# NeuWatch.net
KiCad netlist of a schematic drawn in EAGLE
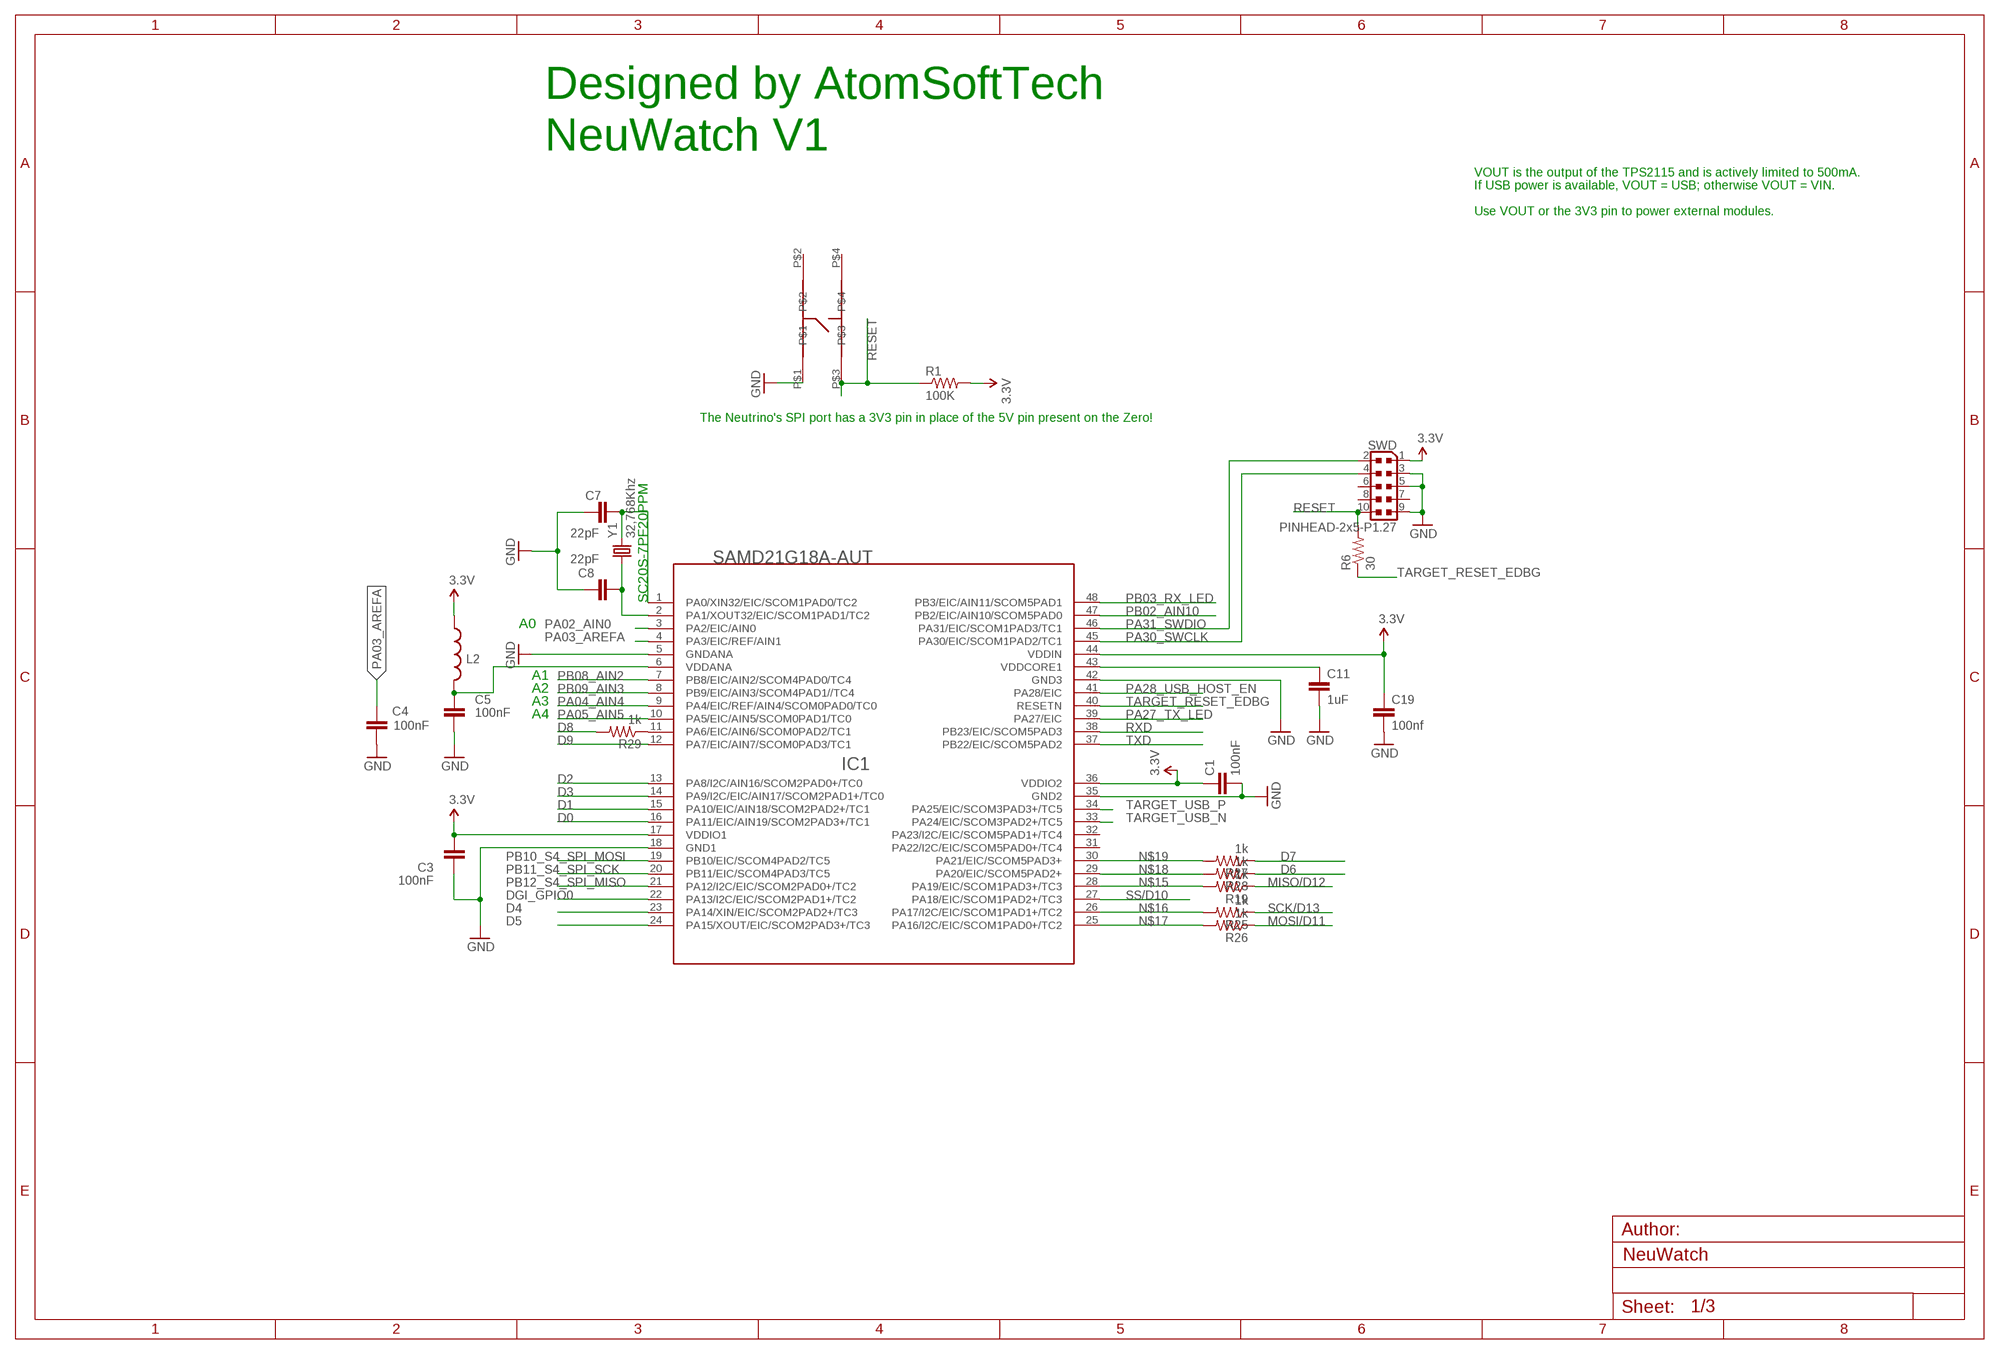
[diagram p0: schematic, sheet 1]
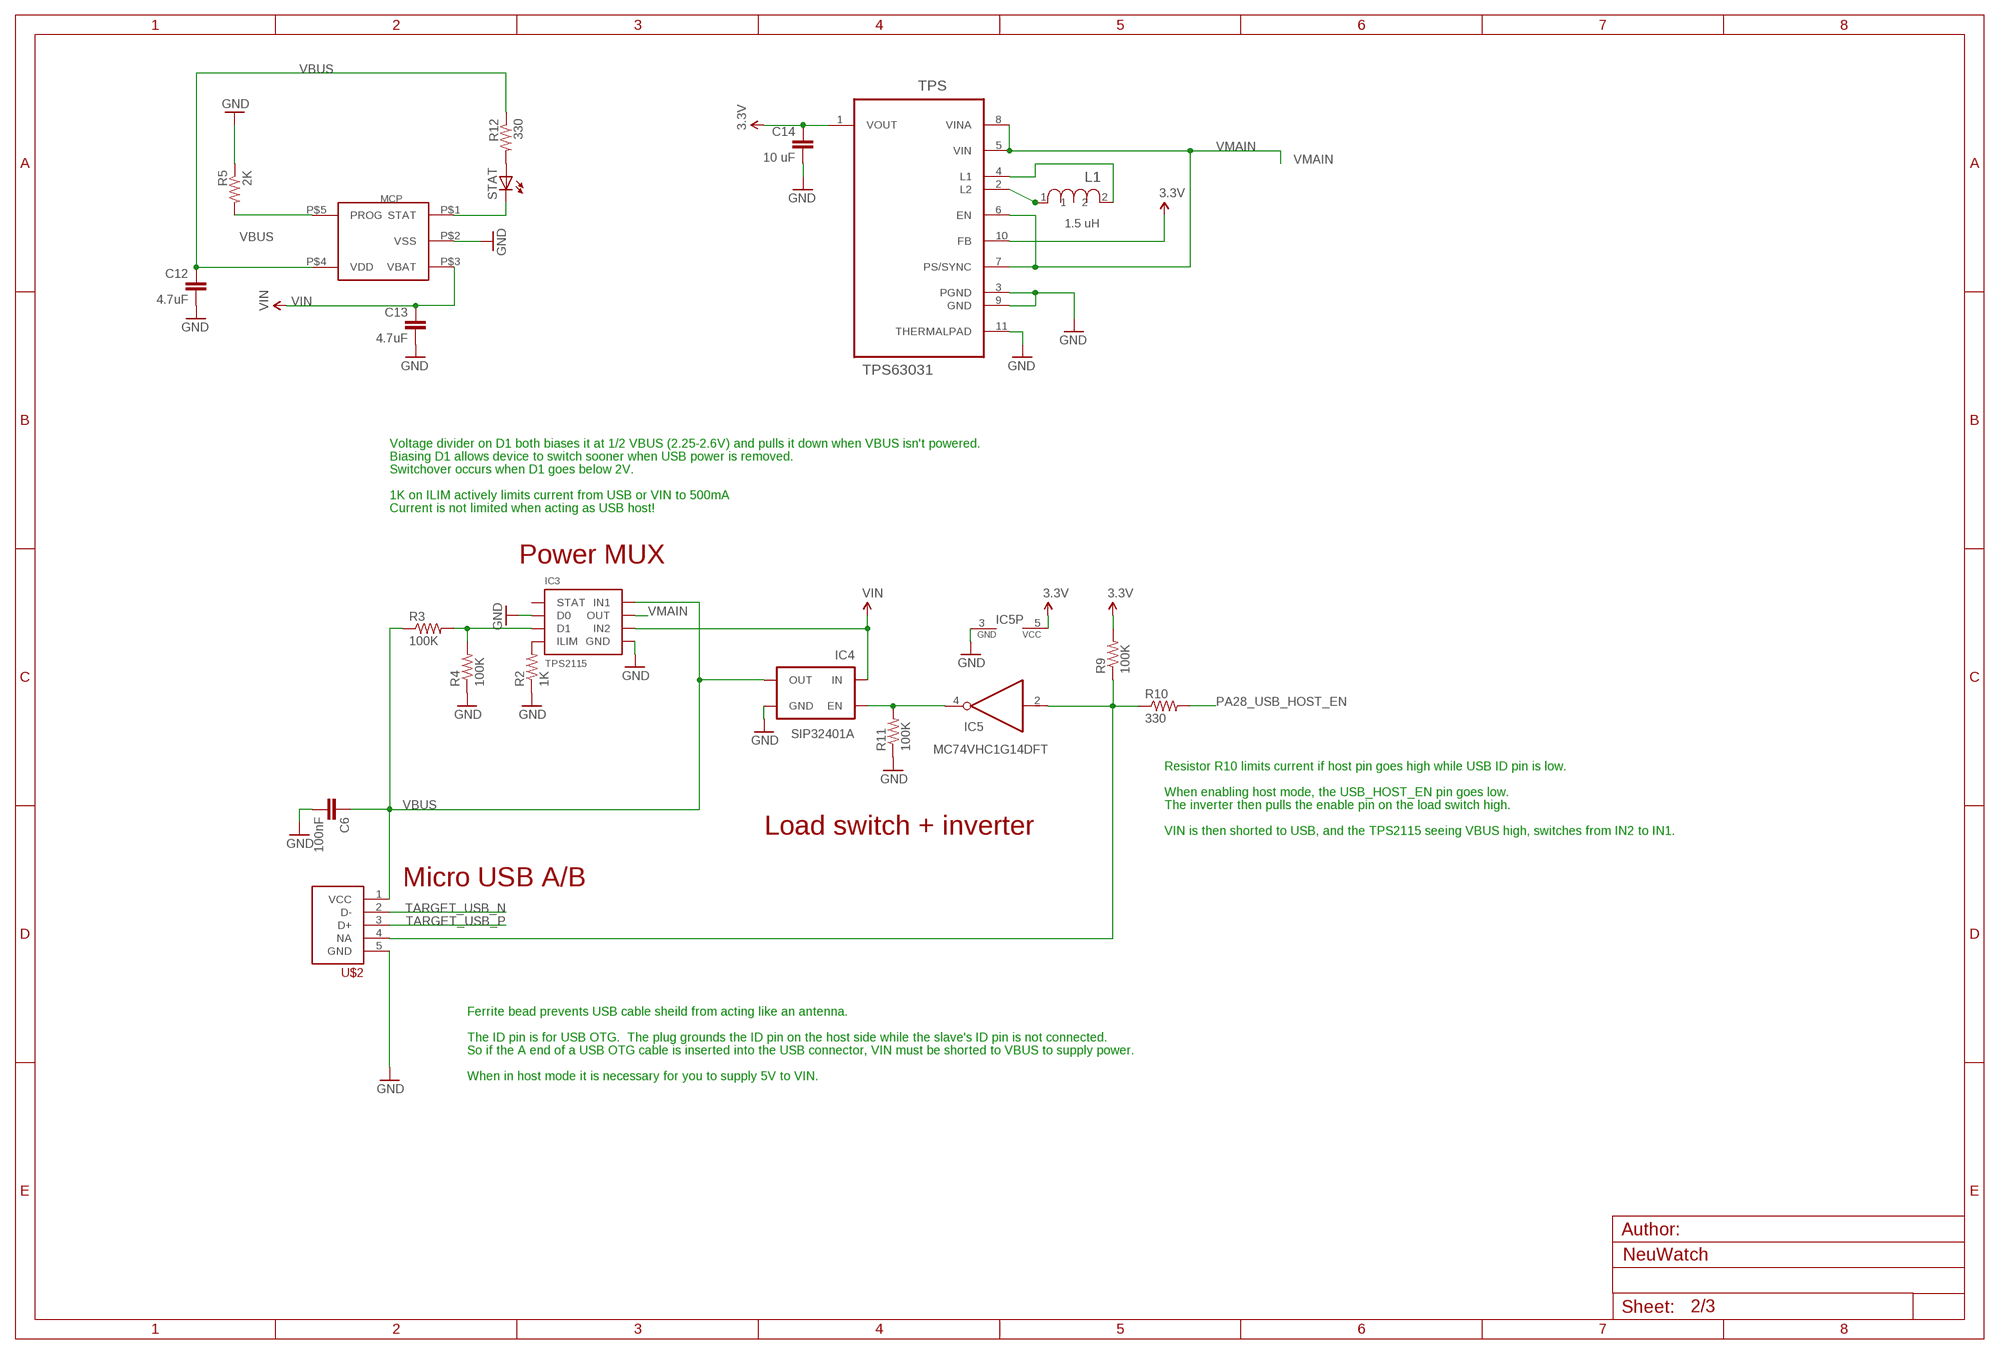
[diagram p1: schematic, sheet 2]
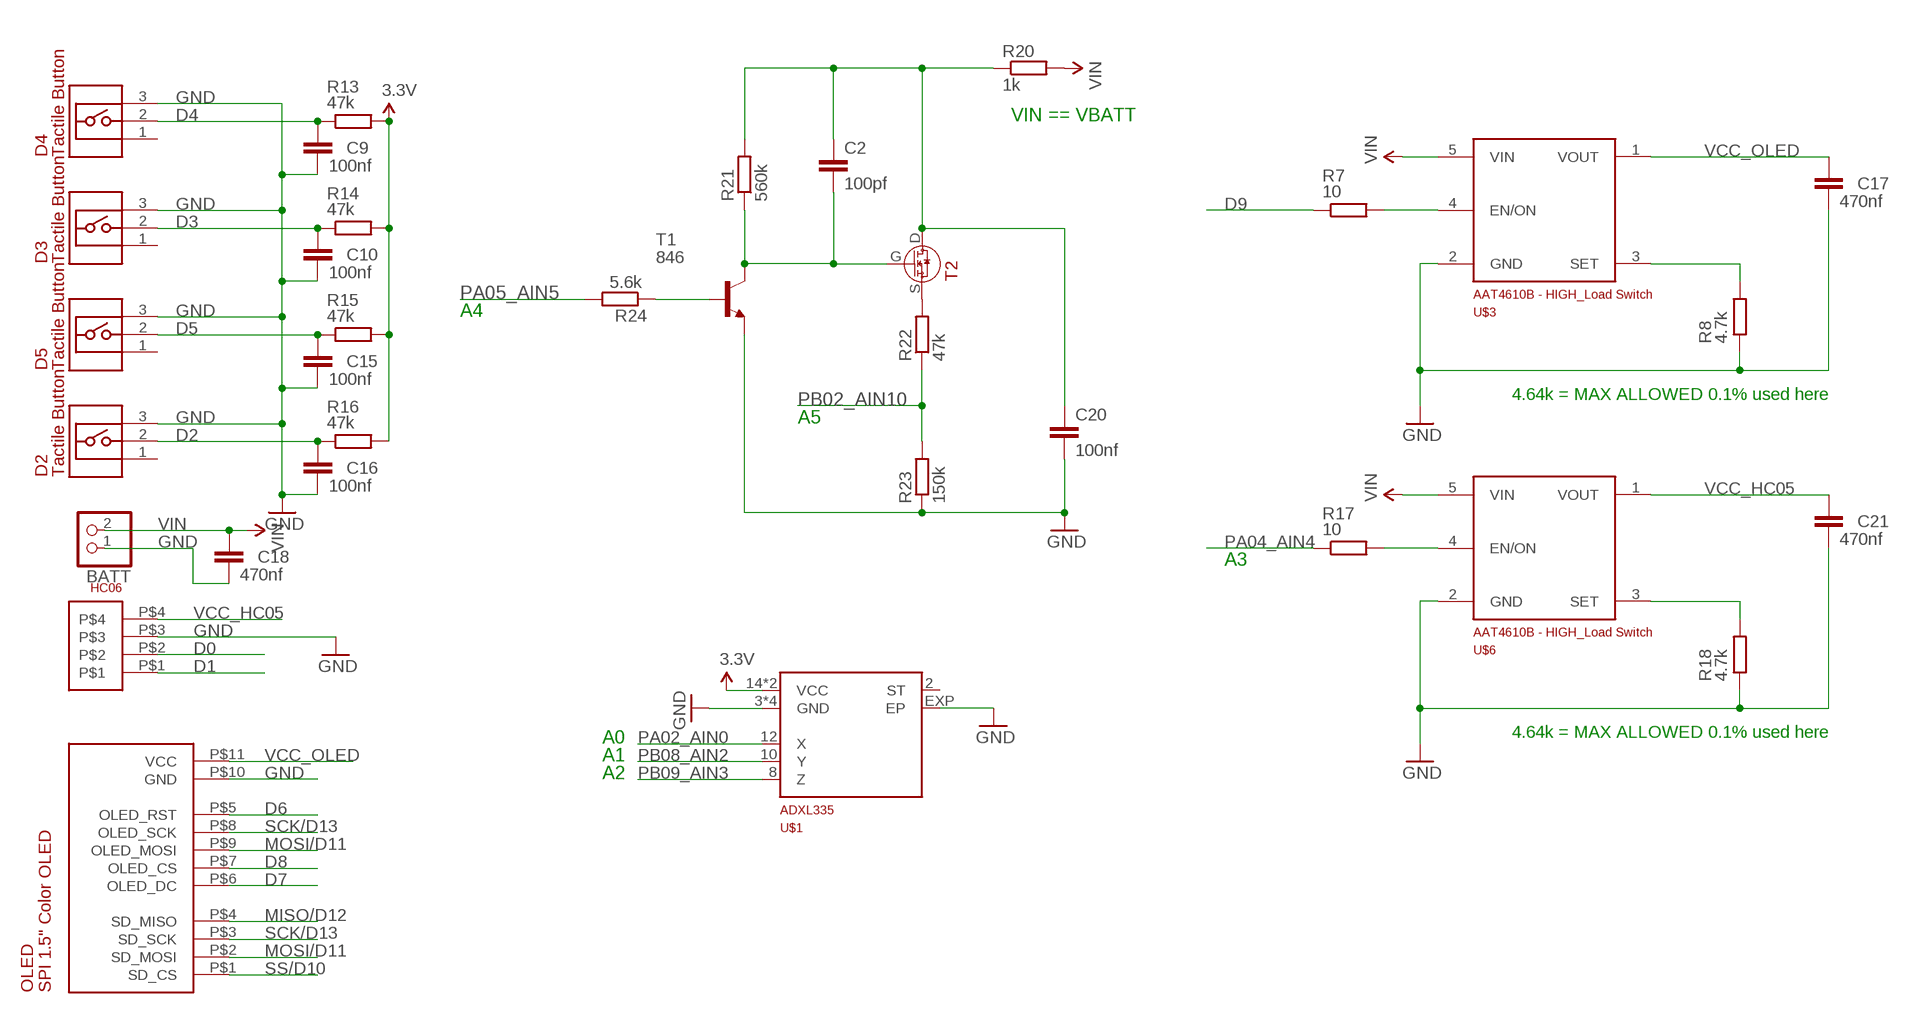
[diagram p2: schematic, sheet 3]

(export (version "E")
  (design (tool "Eeschema 10.0.6"))
  (components
    (comp (ref "C1")
      (value "100nF")
      (footprint "eagle-import:C0402")
      (libsource (lib "eagle-import") (part "CAPACITORC0402"))
    )
    (comp (ref "C3")
      (value "100nF")
      (footprint "eagle-import:C0402")
      (libsource (lib "eagle-import") (part "CAPACITORC0402"))
    )
    (comp (ref "C4")
      (value "100nF")
      (footprint "eagle-import:C0402")
      (libsource (lib "eagle-import") (part "CAPACITORC0402"))
    )
    (comp (ref "C5")
      (value "100nF")
      (footprint "eagle-import:C0402")
      (libsource (lib "eagle-import") (part "CAPACITORC0402"))
    )
    (comp (ref "C7")
      (value "22pF")
      (footprint "eagle-import:C0402")
      (libsource (lib "eagle-import") (part "CAPACITORC0402"))
    )
    (comp (ref "C8")
      (value "22pF")
      (footprint "eagle-import:C0402")
      (libsource (lib "eagle-import") (part "CAPACITORC0402"))
    )
    (comp (ref "C11")
      (value "1uF")
      (footprint "eagle-import:C0402")
      (libsource (lib "eagle-import") (part "CAPACITORC0402"))
    )
    (comp (ref "C19")
      (value "100nf")
      (footprint "eagle-import:C0402")
      (libsource (lib "eagle-import") (part "CAPACITORC0402"))
    )
    (comp (ref "IC1")
      (value "SAMD21G18A-AUT")
      (footprint "eagle-import:INTEGRATEDCIRCUITS_TQFP48-7X7")
      (libsource (lib "eagle-import") (part "INTEGRATEDCIRCUITS_1792_SAMD21G18A-AUT"))
    )
    (comp (ref "L2")
      (value "INDUCTOR0603-TDK")
      (footprint "eagle-import:0603-TDK")
      (libsource (lib "eagle-import") (part "INDUCTOR0603-TDK"))
    )
    (comp (ref "R1")
      (value "100K")
      (footprint "eagle-import:R0402")
      (libsource (lib "eagle-import") (part "R-US_R0402"))
    )
    (comp (ref "R6")
      (value "30")
      (footprint "eagle-import:R0402")
      (libsource (lib "eagle-import") (part "R-US_R0402"))
    )
    (comp (ref "R19")
      (value "1k")
      (footprint "eagle-import:R0402")
      (libsource (lib "eagle-import") (part "R-US_R0402"))
    )
    (comp (ref "R25")
      (value "1k")
      (footprint "eagle-import:R0402")
      (libsource (lib "eagle-import") (part "R-US_R0402"))
    )
    (comp (ref "R26")
      (value "1k")
      (footprint "eagle-import:R0402")
      (libsource (lib "eagle-import") (part "R-US_R0402"))
    )
    (comp (ref "R27")
      (value "1k")
      (footprint "eagle-import:R0402")
      (libsource (lib "eagle-import") (part "R-US_R0402"))
    )
    (comp (ref "R28")
      (value "1k")
      (footprint "eagle-import:R0402")
      (libsource (lib "eagle-import") (part "R-US_R0402"))
    )
    (comp (ref "R29")
      (value "1k")
      (footprint "eagle-import:R0402")
      (libsource (lib "eagle-import") (part "R-US_R0402"))
    )
    (comp (ref "RESET")
      (value "TACTILE_SWITCH")
      (footprint "eagle-import:PTS540")
      (libsource (lib "eagle-import") (part "TACTILE_SWITCH"))
    )
    (comp (ref "SWD")
      (value "PINHEAD-2x5-P1.27")
      (footprint "eagle-import:ARDUINO-NEUTRINO-082_CONNETTORI_PINHEAD-2X5-P127")
      (libsource (lib "eagle-import") (part "ARDUINO-NEUTRINO-082_CONNETTORI_0171_PH127-205DF055G00A"))
    )
    (comp (ref "Y1")
      (value "32,768Khz")
      (footprint "eagle-import:CRYSTAL-SMD-2.0X1.2")
      (libsource (lib "eagle-import") (part "CRYSTAL2012"))
    )
    (comp (ref "C6")
      (value "100nF")
      (footprint "eagle-import:C0402")
      (libsource (lib "eagle-import") (part "CAPACITORC0402"))
    )
    (comp (ref "C12")
      (value "4.7uF")
      (footprint "eagle-import:C0402")
      (libsource (lib "eagle-import") (part "CAPACITORC0402"))
    )
    (comp (ref "C13")
      (value "4.7uF")
      (footprint "eagle-import:C0402")
      (libsource (lib "eagle-import") (part "CAPACITORC0402"))
    )
    (comp (ref "C14")
      (value "10 uF")
      (footprint "eagle-import:C0402")
      (libsource (lib "eagle-import") (part "CAPACITORC0402"))
    )
    (comp (ref "IC3")
      (value "TPS2115")
      (footprint "eagle-import:8-VDFN")
      (libsource (lib "eagle-import") (part "TPS2115"))
    )
    (comp (ref "IC4")
      (value "SIP32401A")
      (footprint "eagle-import:TDFN4")
      (libsource (lib "eagle-import") (part "SIP32401A"))
    )
    (comp (ref "IC5")
      (value "MC74VHC1G14DFT")
      (footprint "eagle-import:SC70-5")
      (libsource (lib "eagle-import") (part "741G04DCKAHC"))
    )
    (comp (ref "L1")
      (value "1.5 uH")
      (footprint "eagle-import:INDC1610X12N")
      (fields (field (name "MPN") "PM0603-R12J-RC") (field (name "TOLERANCE") "±5 %"))
      (libsource (lib "eagle-import") (part "PM0603-R12J-RC"))
    )
    (comp (ref "MCP")
      (value "MCP73831")
      (footprint "eagle-import:5PIN_SOT23")
      (libsource (lib "eagle-import") (part "MCP73831"))
    )
    (comp (ref "R2")
      (value "1K")
      (footprint "eagle-import:R0402")
      (libsource (lib "eagle-import") (part "R-US_R0402"))
    )
    (comp (ref "R3")
      (value "100K")
      (footprint "eagle-import:R0402")
      (libsource (lib "eagle-import") (part "R-US_R0402"))
    )
    (comp (ref "R4")
      (value "100K")
      (footprint "eagle-import:R0402")
      (libsource (lib "eagle-import") (part "R-US_R0402"))
    )
    (comp (ref "R5")
      (value "2K")
      (footprint "eagle-import:R0402")
      (libsource (lib "eagle-import") (part "rcl_R-US_R0402"))
    )
    (comp (ref "R9")
      (value "100K")
      (footprint "eagle-import:R0402")
      (libsource (lib "eagle-import") (part "R-US_R0402"))
    )
    (comp (ref "R10")
      (value "330")
      (footprint "eagle-import:R0402")
      (libsource (lib "eagle-import") (part "R-US_R0402"))
    )
    (comp (ref "R11")
      (value "100K")
      (footprint "eagle-import:R0402")
      (libsource (lib "eagle-import") (part "R-US_R0402"))
    )
    (comp (ref "R12")
      (value "330")
      (footprint "eagle-import:R0402")
      (libsource (lib "eagle-import") (part "rcl_R-US_R0402"))
    )
    (comp (ref "STAT")
      (value "LEDSML0603")
      (footprint "eagle-import:SML0603")
      (libsource (lib "eagle-import") (part "LEDSML0603"))
    )
    (comp (ref "TPS")
      (value "TPS63031")
      (footprint "eagle-import:SON50P260X260X80-11N")
      (fields (field (name "MPN") "TPS63031"))
      (libsource (lib "eagle-import") (part "TPS63031"))
    )
    (comp (ref "U$2")
      (value "USB_GENERIC_CHEAT")
      (footprint "eagle-import:1LFS")
      (libsource (lib "eagle-import") (part "USB_GENERIC_CHEAT"))
    )
    (comp (ref "BATT")
      (value "PINHD-1X2")
      (footprint "eagle-import:1X02")
      (libsource (lib "eagle-import") (part "PINHD-1X2"))
    )
    (comp (ref "C2")
      (value "100pf")
      (footprint "eagle-import:C0402")
      (libsource (lib "eagle-import") (part "CAPACITORC0402"))
    )
    (comp (ref "C9")
      (value "100nf")
      (footprint "eagle-import:C0402")
      (libsource (lib "eagle-import") (part "CAPACITORC0402"))
    )
    (comp (ref "C10")
      (value "100nf")
      (footprint "eagle-import:C0402")
      (libsource (lib "eagle-import") (part "CAPACITORC0402"))
    )
    (comp (ref "C15")
      (value "100nf")
      (footprint "eagle-import:C0402")
      (libsource (lib "eagle-import") (part "CAPACITORC0402"))
    )
    (comp (ref "C16")
      (value "100nf")
      (footprint "eagle-import:C0402")
      (libsource (lib "eagle-import") (part "CAPACITORC0402"))
    )
    (comp (ref "C17")
      (value "470nf")
      (footprint "eagle-import:C0402")
      (libsource (lib "eagle-import") (part "CAPACITORC0402"))
    )
    (comp (ref "C18")
      (value "470nf")
      (footprint "eagle-import:C0402")
      (libsource (lib "eagle-import") (part "CAPACITORC0402"))
    )
    (comp (ref "C20")
      (value "100nf")
      (footprint "eagle-import:C0402")
      (libsource (lib "eagle-import") (part "CAPACITORC0402"))
    )
    (comp (ref "C21")
      (value "470nf")
      (footprint "eagle-import:C0402")
      (libsource (lib "eagle-import") (part "CAPACITORC0402"))
    )
    (comp (ref "D2")
      (value "BUTTON_P0")
      (footprint "eagle-import:P021301")
      (libsource (lib "eagle-import") (part "BUTTON_P0"))
    )
    (comp (ref "D3")
      (value "BUTTON_P0")
      (footprint "eagle-import:P021301")
      (libsource (lib "eagle-import") (part "BUTTON_P0"))
    )
    (comp (ref "D4")
      (value "BUTTON_P0")
      (footprint "eagle-import:P021301")
      (libsource (lib "eagle-import") (part "BUTTON_P0"))
    )
    (comp (ref "D5")
      (value "BUTTON_P0")
      (footprint "eagle-import:P021301")
      (libsource (lib "eagle-import") (part "BUTTON_P0"))
    )
    (comp (ref "HC06")
      (value "1X4")
      (footprint "eagle-import:1B4")
      (libsource (lib "eagle-import") (part "1X4"))
    )
    (comp (ref "OLED")
      (value "1.5-OLED")
      (footprint "eagle-import:1.5OLED")
      (libsource (lib "eagle-import") (part "1.5-OLED"))
    )
    (comp (ref "R7")
      (value "10")
      (footprint "eagle-import:R0402")
      (libsource (lib "eagle-import") (part "R-EU_R0402"))
    )
    (comp (ref "R8")
      (value "4.7k")
      (footprint "eagle-import:R0402")
      (libsource (lib "eagle-import") (part "R-EU_R0402"))
    )
    (comp (ref "R13")
      (value "47k")
      (footprint "eagle-import:R0402")
      (libsource (lib "eagle-import") (part "R-EU_R0402"))
    )
    (comp (ref "R14")
      (value "47k")
      (footprint "eagle-import:R0402")
      (libsource (lib "eagle-import") (part "R-EU_R0402"))
    )
    (comp (ref "R15")
      (value "47k")
      (footprint "eagle-import:R0402")
      (libsource (lib "eagle-import") (part "R-EU_R0402"))
    )
    (comp (ref "R16")
      (value "47k")
      (footprint "eagle-import:R0402")
      (libsource (lib "eagle-import") (part "R-EU_R0402"))
    )
    (comp (ref "R17")
      (value "10")
      (footprint "eagle-import:R0402")
      (libsource (lib "eagle-import") (part "R-EU_R0402"))
    )
    (comp (ref "R18")
      (value "4.7k")
      (footprint "eagle-import:R0402")
      (libsource (lib "eagle-import") (part "R-EU_R0402"))
    )
    (comp (ref "R20")
      (value "1k")
      (footprint "eagle-import:R0402")
      (libsource (lib "eagle-import") (part "R-EU_R0402"))
    )
    (comp (ref "R21")
      (value "560k")
      (footprint "eagle-import:R0402")
      (libsource (lib "eagle-import") (part "R-EU_R0402"))
    )
    (comp (ref "R22")
      (value "47k")
      (footprint "eagle-import:R0402")
      (libsource (lib "eagle-import") (part "R-EU_R0402"))
    )
    (comp (ref "R23")
      (value "150k")
      (footprint "eagle-import:R0402")
      (libsource (lib "eagle-import") (part "R-EU_R0402"))
    )
    (comp (ref "R24")
      (value "5.6k")
      (footprint "eagle-import:R0402")
      (libsource (lib "eagle-import") (part "R-EU_R0402"))
    )
    (comp (ref "T1")
      (value "846")
      (footprint "eagle-import:SOT23-BEC")
      (libsource (lib "eagle-import") (part "-NPN-SOT23-BECBC846BLT1"))
    )
    (comp (ref "T2")
      (value "2N7002")
      (footprint "eagle-import:MOSFET")
      (libsource (lib "eagle-import") (part "2N7002_ALT"))
    )
    (comp (ref "U$1")
      (value "ADXL335")
      (footprint "eagle-import:16LFCSP")
      (libsource (lib "eagle-import") (part "ADXL335"))
    )
    (comp (ref "U$3")
      (value "AAT4610B")
      (footprint "eagle-import:SOT23-5")
      (libsource (lib "eagle-import") (part "AAT4610B"))
    )
    (comp (ref "U$6")
      (value "AAT4610B")
      (footprint "eagle-import:SOT23-5")
      (libsource (lib "eagle-import") (part "AAT4610B"))
    )
  )
  (nets
    (net (code "1") (name "3.3V") (class "Default")
      (node (ref "C1") (pin "1") (pinfunction "1_1") (pintype "passive"))
      (node (ref "C14") (pin "1") (pinfunction "1_1") (pintype "passive"))
      (node (ref "C19") (pin "1") (pinfunction "1_1") (pintype "passive"))
      (node (ref "C3") (pin "2") (pinfunction "2_2") (pintype "passive"))
      (node (ref "IC1") (pin "17") (pinfunction "VDDIO1_17") (pintype "power_in"))
      (node (ref "IC1") (pin "36") (pinfunction "VDDIO2_36") (pintype "power_in"))
      (node (ref "IC1") (pin "44") (pinfunction "VDDIN_44") (pintype "power_in"))
      (node (ref "IC5") (pin "5") (pinfunction "VCC_5") (pintype "power_in"))
      (node (ref "L2") (pin "1") (pinfunction "1_1") (pintype "passive"))
      (node (ref "R1") (pin "2") (pinfunction "2_2") (pintype "passive"))
      (node (ref "R13") (pin "2") (pinfunction "2_2") (pintype "passive"))
      (node (ref "R14") (pin "2") (pinfunction "2_2") (pintype "passive"))
      (node (ref "R15") (pin "2") (pinfunction "2_2") (pintype "passive"))
      (node (ref "R16") (pin "2") (pinfunction "2_2") (pintype "passive"))
      (node (ref "R9") (pin "2") (pinfunction "2_2") (pintype "passive"))
      (node (ref "SWD") (pin "1") (pinfunction "1_1") (pintype "passive"))
      (node (ref "TPS") (pin "1") (pinfunction "VOUT_1") (pintype "output"))
      (node (ref "TPS") (pin "10") (pinfunction "FB_10") (pintype "input"))
      (node (ref "U$1") (pin "14") (pinfunction "VCC_14") (pintype "power_in"))
      (node (ref "U$1") (pin "15") (pinfunction "VCC_15") (pintype "power_in"))
    )
    (net (code "2") (name "D0") (class "Default")
      (node (ref "HC06") (pin "P$2") (pinfunction "P$2_P$2") (pintype "bidirectional"))
      (node (ref "IC1") (pin "16") (pinfunction "PA11/EIC/AIN19/SCOM2PAD3+/TC1_16") (pintype "bidirectional"))
    )
    (net (code "3") (name "D1") (class "Default")
      (node (ref "HC06") (pin "P$1") (pinfunction "P$1_P$1") (pintype "bidirectional"))
      (node (ref "IC1") (pin "15") (pinfunction "PA10/EIC/AIN18/SCOM2PAD2+/TC1_15") (pintype "bidirectional"))
    )
    (net (code "4") (name "D2") (class "Default")
      (node (ref "C16") (pin "1") (pinfunction "1_1") (pintype "passive"))
      (node (ref "D2") (pin "2") (pinfunction "2_2") (pintype "bidirectional"))
      (node (ref "IC1") (pin "13") (pinfunction "PA8/I2C/AIN16/SCOM2PAD0+/TC0_13") (pintype "bidirectional"))
      (node (ref "R16") (pin "1") (pinfunction "1_1") (pintype "passive"))
    )
    (net (code "5") (name "D3") (class "Default")
      (node (ref "C10") (pin "1") (pinfunction "1_1") (pintype "passive"))
      (node (ref "D3") (pin "2") (pinfunction "2_2") (pintype "bidirectional"))
      (node (ref "IC1") (pin "14") (pinfunction "PA9/I2C/EIC/AIN17/SCOM2PAD1+/TC0_14") (pintype "bidirectional"))
      (node (ref "R14") (pin "1") (pinfunction "1_1") (pintype "passive"))
    )
    (net (code "6") (name "D4") (class "Default")
      (node (ref "C9") (pin "1") (pinfunction "1_1") (pintype "passive"))
      (node (ref "D4") (pin "2") (pinfunction "2_2") (pintype "bidirectional"))
      (node (ref "IC1") (pin "23") (pinfunction "PA14/XIN/EIC/SCOM2PAD2+/TC3_23") (pintype "bidirectional"))
      (node (ref "R13") (pin "1") (pinfunction "1_1") (pintype "passive"))
    )
    (net (code "7") (name "D5") (class "Default")
      (node (ref "C15") (pin "1") (pinfunction "1_1") (pintype "passive"))
      (node (ref "D5") (pin "2") (pinfunction "2_2") (pintype "bidirectional"))
      (node (ref "IC1") (pin "24") (pinfunction "PA15/XOUT/EIC/SCOM2PAD3+/TC3_24") (pintype "bidirectional"))
      (node (ref "R15") (pin "1") (pinfunction "1_1") (pintype "passive"))
    )
    (net (code "8") (name "D6") (class "Default")
      (node (ref "OLED") (pin "P$5") (pinfunction "OLED_RST_P$5") (pintype "bidirectional"))
      (node (ref "R28") (pin "1") (pinfunction "1_1") (pintype "passive"))
    )
    (net (code "9") (name "D7") (class "Default")
      (node (ref "OLED") (pin "P$6") (pinfunction "OLED_DC_P$6") (pintype "bidirectional"))
      (node (ref "R27") (pin "1") (pinfunction "1_1") (pintype "passive"))
    )
    (net (code "10") (name "D8") (class "Default")
      (node (ref "OLED") (pin "P$7") (pinfunction "OLED_CS_P$7") (pintype "bidirectional"))
      (node (ref "R29") (pin "2") (pinfunction "2_2") (pintype "passive"))
    )
    (net (code "11") (name "D9") (class "Default")
      (node (ref "IC1") (pin "12") (pinfunction "PA7/EIC/AIN7/SCOM0PAD3/TC1_12") (pintype "bidirectional"))
      (node (ref "R7") (pin "1") (pinfunction "1_1") (pintype "passive"))
    )
    (net (code "12") (name "DGI_GPIO0") (class "Default")
      (node (ref "IC1") (pin "22") (pinfunction "PA13/I2C/EIC/SCOM2PAD1+/TC2_22") (pintype "bidirectional"))
    )
    (net (code "13") (name "GND") (class "Default")
      (node (ref "BATT") (pin "1") (pinfunction "1_1") (pintype "passive"))
      (node (ref "C1") (pin "2") (pinfunction "2_2") (pintype "passive"))
      (node (ref "C10") (pin "2") (pinfunction "2_2") (pintype "passive"))
      (node (ref "C11") (pin "2") (pinfunction "2_2") (pintype "passive"))
      (node (ref "C12") (pin "2") (pinfunction "2_2") (pintype "passive"))
      (node (ref "C13") (pin "2") (pinfunction "2_2") (pintype "passive"))
      (node (ref "C14") (pin "2") (pinfunction "2_2") (pintype "passive"))
      (node (ref "C15") (pin "2") (pinfunction "2_2") (pintype "passive"))
      (node (ref "C16") (pin "2") (pinfunction "2_2") (pintype "passive"))
      (node (ref "C17") (pin "2") (pinfunction "2_2") (pintype "passive"))
      (node (ref "C18") (pin "2") (pinfunction "2_2") (pintype "passive"))
      (node (ref "C19") (pin "2") (pinfunction "2_2") (pintype "passive"))
      (node (ref "C20") (pin "2") (pinfunction "2_2") (pintype "passive"))
      (node (ref "C21") (pin "2") (pinfunction "2_2") (pintype "passive"))
      (node (ref "C3") (pin "1") (pinfunction "1_1") (pintype "passive"))
      (node (ref "C4") (pin "2") (pinfunction "2_2") (pintype "passive"))
      (node (ref "C5") (pin "2") (pinfunction "2_2") (pintype "passive"))
      (node (ref "C6") (pin "2") (pinfunction "2_2") (pintype "passive"))
      (node (ref "C7") (pin "1") (pinfunction "1_1") (pintype "passive"))
      (node (ref "C8") (pin "1") (pinfunction "1_1") (pintype "passive"))
      (node (ref "C9") (pin "2") (pinfunction "2_2") (pintype "passive"))
      (node (ref "D2") (pin "3") (pinfunction "3_3") (pintype "bidirectional"))
      (node (ref "D3") (pin "3") (pinfunction "3_3") (pintype "bidirectional"))
      (node (ref "D4") (pin "3") (pinfunction "3_3") (pintype "bidirectional"))
      (node (ref "D5") (pin "3") (pinfunction "3_3") (pintype "bidirectional"))
      (node (ref "HC06") (pin "P$3") (pinfunction "P$3_P$3") (pintype "bidirectional"))
      (node (ref "IC1") (pin "18") (pinfunction "GND1_18") (pintype "power_in"))
      (node (ref "IC1") (pin "35") (pinfunction "GND2_35") (pintype "power_in"))
      (node (ref "IC1") (pin "42") (pinfunction "GND3_42") (pintype "power_in"))
      (node (ref "IC1") (pin "5") (pinfunction "GNDANA_5") (pintype "power_in"))
      (node (ref "IC3") (pin "2") (pinfunction "D0_2") (pintype "bidirectional"))
      (node (ref "IC3") (pin "5") (pinfunction "GND_5") (pintype "bidirectional"))
      (node (ref "IC3") (pin "P0") (pinfunction "GND_P0") (pintype "bidirectional"))
      (node (ref "IC3") (pin "V0") (pinfunction "GND_V0") (pintype "bidirectional"))
      (node (ref "IC3") (pin "V1") (pinfunction "GND_V1") (pintype "bidirectional"))
      (node (ref "IC3") (pin "V2") (pinfunction "GND_V2") (pintype "bidirectional"))
      (node (ref "IC3") (pin "V3") (pinfunction "GND_V3") (pintype "bidirectional"))
      (node (ref "IC3") (pin "V4") (pinfunction "GND_V4") (pintype "bidirectional"))
      (node (ref "IC4") (pin "0") (pinfunction "GND_0") (pintype "power_in"))
      (node (ref "IC4") (pin "2") (pinfunction "GND_2") (pintype "power_in"))
      (node (ref "IC5") (pin "3") (pinfunction "GND_3") (pintype "power_in"))
      (node (ref "MCP") (pin "P$2") (pinfunction "VSS_P$2") (pintype "bidirectional"))
      (node (ref "OLED") (pin "P$10") (pinfunction "GND_P$10") (pintype "bidirectional"))
      (node (ref "R11") (pin "1") (pinfunction "1_1") (pintype "passive"))
      (node (ref "R18") (pin "1") (pinfunction "1_1") (pintype "passive"))
      (node (ref "R2") (pin "1") (pinfunction "1_1") (pintype "passive"))
      (node (ref "R23") (pin "1") (pinfunction "1_1") (pintype "passive"))
      (node (ref "R4") (pin "1") (pinfunction "1_1") (pintype "passive"))
      (node (ref "R5") (pin "1") (pinfunction "1_1") (pintype "passive"))
      (node (ref "R8") (pin "1") (pinfunction "1_1") (pintype "passive"))
      (node (ref "RESET") (pin "P$1") (pinfunction "P$1_P$1") (pintype "bidirectional"))
      (node (ref "SWD") (pin "3") (pinfunction "3_3") (pintype "passive"))
      (node (ref "SWD") (pin "5") (pinfunction "5_5") (pintype "passive"))
      (node (ref "SWD") (pin "9") (pinfunction "9_9") (pintype "passive"))
      (node (ref "T1") (pin "E") (pinfunction "E_E") (pintype "passive"))
      (node (ref "TPS") (pin "11") (pinfunction "THERMALPAD_11") (pintype "passive"))
      (node (ref "TPS") (pin "3") (pinfunction "PGND_3") (pintype "passive"))
      (node (ref "TPS") (pin "9") (pinfunction "GND_9") (pintype "passive"))
      (node (ref "U$1") (pin "3") (pinfunction "GND_3") (pintype "power_in"))
      (node (ref "U$1") (pin "5") (pinfunction "GND_5") (pintype "power_in"))
      (node (ref "U$1") (pin "6") (pinfunction "GND_6") (pintype "power_in"))
      (node (ref "U$1") (pin "7") (pinfunction "GND_7") (pintype "power_in"))
      (node (ref "U$1") (pin "EXP") (pinfunction "EP_EXP") (pintype "power_in"))
      (node (ref "U$2") (pin "5") (pinfunction "GND_5") (pintype "bidirectional"))
      (node (ref "U$3") (pin "2") (pinfunction "GND_2") (pintype "bidirectional"))
      (node (ref "U$6") (pin "2") (pinfunction "GND_2") (pintype "bidirectional"))
    )
    (net (code "14") (name "MISO{slash}D12") (class "Default")
      (node (ref "OLED") (pin "P$4") (pinfunction "SD_MISO_P$4") (pintype "bidirectional"))
      (node (ref "R19") (pin "1") (pinfunction "1_1") (pintype "passive"))
    )
    (net (code "15") (name "MOSI{slash}D11") (class "Default")
      (node (ref "OLED") (pin "P$2") (pinfunction "SD_MOSI_P$2") (pintype "bidirectional"))
      (node (ref "OLED") (pin "P$9") (pinfunction "OLED_MOSI_P$9") (pintype "bidirectional"))
      (node (ref "R26") (pin "1") (pinfunction "1_1") (pintype "passive"))
    )
    (net (code "16") (name "N$15") (class "Default")
      (node (ref "IC1") (pin "28") (pinfunction "PA19/EIC/SCOM1PAD3+/TC3_28") (pintype "bidirectional"))
      (node (ref "R19") (pin "2") (pinfunction "2_2") (pintype "passive"))
    )
    (net (code "17") (name "N$16") (class "Default")
      (node (ref "IC1") (pin "26") (pinfunction "PA17/I2C/EIC/SCOM1PAD1+/TC2_26") (pintype "bidirectional"))
      (node (ref "R25") (pin "2") (pinfunction "2_2") (pintype "passive"))
    )
    (net (code "18") (name "N$17") (class "Default")
      (node (ref "IC1") (pin "25") (pinfunction "PA16/I2C/EIC/SCOM1PAD0+/TC2_25") (pintype "bidirectional"))
      (node (ref "R26") (pin "2") (pinfunction "2_2") (pintype "passive"))
    )
    (net (code "19") (name "N$18") (class "Default")
      (node (ref "IC1") (pin "29") (pinfunction "PA20/EIC/SCOM5PAD2+_29") (pintype "bidirectional"))
      (node (ref "R28") (pin "2") (pinfunction "2_2") (pintype "passive"))
    )
    (net (code "20") (name "N$19") (class "Default")
      (node (ref "IC1") (pin "30") (pinfunction "PA21/EIC/SCOM5PAD3+_30") (pintype "bidirectional"))
      (node (ref "R27") (pin "2") (pinfunction "2_2") (pintype "passive"))
    )
    (net (code "21") (name "Net-(C2-Pad1)") (class "Default")
      (node (ref "C2") (pin "1") (pinfunction "1_1") (pintype "passive"))
      (node (ref "C20") (pin "1") (pinfunction "1_1") (pintype "passive"))
      (node (ref "R20") (pin "1") (pinfunction "1_1") (pintype "passive"))
      (node (ref "R21") (pin "2") (pinfunction "2_2") (pintype "passive"))
      (node (ref "T2") (pin "D") (pinfunction "D_D") (pintype "bidirectional"))
    )
    (net (code "22") (name "Net-(C2-Pad2)") (class "Default")
      (node (ref "C2") (pin "2") (pinfunction "2_2") (pintype "passive"))
      (node (ref "R21") (pin "1") (pinfunction "1_1") (pintype "passive"))
      (node (ref "T1") (pin "C") (pinfunction "C_C") (pintype "passive"))
      (node (ref "T2") (pin "G") (pinfunction "G_G") (pintype "bidirectional"))
    )
    (net (code "23") (name "Net-(IC1-PA0{slash}XIN32{slash}EIC{slash}SCOM1PAD0{slash}TC2)") (class "Default")
      (node (ref "C7") (pin "2") (pinfunction "2_2") (pintype "passive"))
      (node (ref "IC1") (pin "1") (pinfunction "PA0/XIN32/EIC/SCOM1PAD0/TC2_1") (pintype "bidirectional"))
      (node (ref "Y1") (pin "2") (pinfunction "2_2") (pintype "passive"))
    )
    (net (code "24") (name "Net-(IC1-PA1{slash}XOUT32{slash}EIC{slash}SCOM1PAD1{slash}TC2)") (class "Default")
      (node (ref "C8") (pin "2") (pinfunction "2_2") (pintype "passive"))
      (node (ref "IC1") (pin "2") (pinfunction "PA1/XOUT32/EIC/SCOM1PAD1/TC2_2") (pintype "bidirectional"))
      (node (ref "Y1") (pin "1") (pinfunction "1_1") (pintype "passive"))
    )
    (net (code "25") (name "Net-(IC1-PA6{slash}EIC{slash}AIN6{slash}SCOM0PAD2{slash}TC1)") (class "Default")
      (node (ref "IC1") (pin "11") (pinfunction "PA6/EIC/AIN6/SCOM0PAD2/TC1_11") (pintype "bidirectional"))
      (node (ref "R29") (pin "1") (pinfunction "1_1") (pintype "passive"))
    )
    (net (code "26") (name "Net-(IC1-VDDANA)") (class "Default")
      (node (ref "C5") (pin "1") (pinfunction "1_1") (pintype "passive"))
      (node (ref "IC1") (pin "6") (pinfunction "VDDANA_6") (pintype "power_in"))
      (node (ref "L2") (pin "2") (pinfunction "2_2") (pintype "passive"))
    )
    (net (code "27") (name "Net-(IC1-VDDCORE1)") (class "Default")
      (node (ref "C11") (pin "1") (pinfunction "1_1") (pintype "passive"))
      (node (ref "IC1") (pin "43") (pinfunction "VDDCORE1_43") (pintype "input"))
    )
    (net (code "28") (name "Net-(IC3-D1)") (class "Default")
      (node (ref "IC3") (pin "3") (pinfunction "D1_3") (pintype "bidirectional"))
      (node (ref "R3") (pin "2") (pinfunction "2_2") (pintype "passive"))
      (node (ref "R4") (pin "2") (pinfunction "2_2") (pintype "passive"))
    )
    (net (code "29") (name "Net-(IC3-ILIM)") (class "Default")
      (node (ref "IC3") (pin "4") (pinfunction "ILIM_4") (pintype "bidirectional"))
      (node (ref "R2") (pin "2") (pinfunction "2_2") (pintype "passive"))
    )
    (net (code "30") (name "Net-(IC4-EN)") (class "Default")
      (node (ref "IC4") (pin "4") (pinfunction "EN_4") (pintype "input"))
      (node (ref "IC5") (pin "4") (pinfunction "O_4") (pintype "output"))
      (node (ref "R11") (pin "2") (pinfunction "2_2") (pintype "passive"))
    )
    (net (code "31") (name "Net-(IC5A-I)") (class "Default")
      (node (ref "IC5") (pin "2") (pinfunction "I_2") (pintype "input"))
      (node (ref "R10") (pin "1") (pinfunction "1_1") (pintype "passive"))
      (node (ref "R9") (pin "1") (pinfunction "1_1") (pintype "passive"))
      (node (ref "U$2") (pin "4") (pinfunction "NA_4") (pintype "bidirectional"))
    )
    (net (code "32") (name "Net-(MCP-PROG)") (class "Default")
      (node (ref "MCP") (pin "P$5") (pinfunction "PROG_P$5") (pintype "bidirectional"))
      (node (ref "R5") (pin "2") (pinfunction "2_2") (pintype "passive"))
    )
    (net (code "33") (name "Net-(MCP-STAT)") (class "Default")
      (node (ref "MCP") (pin "P$1") (pinfunction "STAT_P$1") (pintype "bidirectional"))
      (node (ref "STAT") (pin "C") (pinfunction "C_C") (pintype "passive"))
    )
    (net (code "34") (name "Net-(R12-Pad2)") (class "Default")
      (node (ref "R12") (pin "2") (pinfunction "2_2") (pintype "passive"))
      (node (ref "STAT") (pin "A") (pinfunction "A_A") (pintype "passive"))
    )
    (net (code "35") (name "Net-(R22-Pad2)") (class "Default")
      (node (ref "R22") (pin "2") (pinfunction "2_2") (pintype "passive"))
      (node (ref "T2") (pin "S") (pinfunction "S_S") (pintype "bidirectional"))
    )
    (net (code "36") (name "Net-(R24-Pad1)") (class "Default")
      (node (ref "R24") (pin "1") (pinfunction "1_1") (pintype "passive"))
      (node (ref "T1") (pin "B") (pinfunction "B_B") (pintype "passive"))
    )
    (net (code "37") (name "Net-(TPS-L1)") (class "Default")
      (node (ref "L1") (pin "2") (pinfunction "2_2") (pintype "passive"))
      (node (ref "TPS") (pin "4") (pinfunction "L1_4") (pintype "input"))
    )
    (net (code "38") (name "Net-(TPS-L2)") (class "Default")
      (node (ref "L1") (pin "1") (pinfunction "1_1") (pintype "passive"))
      (node (ref "TPS") (pin "2") (pinfunction "L2_2") (pintype "input"))
    )
    (net (code "39") (name "Net-(U$3-EN{slash}ON)") (class "Default")
      (node (ref "R7") (pin "2") (pinfunction "2_2") (pintype "passive"))
      (node (ref "U$3") (pin "4") (pinfunction "EN/ON_4") (pintype "bidirectional"))
    )
    (net (code "40") (name "Net-(U$3-SET)") (class "Default")
      (node (ref "R8") (pin "2") (pinfunction "2_2") (pintype "passive"))
      (node (ref "U$3") (pin "3") (pinfunction "SET_3") (pintype "bidirectional"))
    )
    (net (code "41") (name "Net-(U$6-EN{slash}ON)") (class "Default")
      (node (ref "R17") (pin "2") (pinfunction "2_2") (pintype "passive"))
      (node (ref "U$6") (pin "4") (pinfunction "EN/ON_4") (pintype "bidirectional"))
    )
    (net (code "42") (name "Net-(U$6-SET)") (class "Default")
      (node (ref "R18") (pin "2") (pinfunction "2_2") (pintype "passive"))
      (node (ref "U$6") (pin "3") (pinfunction "SET_3") (pintype "bidirectional"))
    )
    (net (code "43") (name "PA02_AIN0") (class "Default")
      (node (ref "IC1") (pin "3") (pinfunction "PA2/EIC/AIN0_3") (pintype "bidirectional"))
      (node (ref "U$1") (pin "12") (pinfunction "X_12") (pintype "power_in"))
    )
    (net (code "44") (name "PA03_AREFA") (class "Default")
      (node (ref "C4") (pin "1") (pinfunction "1_1") (pintype "passive"))
      (node (ref "IC1") (pin "4") (pinfunction "PA3/EIC/REF/AIN1_4") (pintype "bidirectional"))
    )
    (net (code "45") (name "PA04_AIN4") (class "Default")
      (node (ref "IC1") (pin "9") (pinfunction "PA4/EIC/REF/AIN4/SCOM0PAD0/TC0_9") (pintype "bidirectional"))
      (node (ref "R17") (pin "1") (pinfunction "1_1") (pintype "passive"))
    )
    (net (code "46") (name "PA05_AIN5") (class "Default")
      (node (ref "IC1") (pin "10") (pinfunction "PA5/EIC/AIN5/SCOM0PAD1/TC0_10") (pintype "bidirectional"))
      (node (ref "R24") (pin "2") (pinfunction "2_2") (pintype "passive"))
    )
    (net (code "47") (name "PA27_TX_LED") (class "Default")
      (node (ref "IC1") (pin "39") (pinfunction "PA27/EIC_39") (pintype "bidirectional"))
    )
    (net (code "48") (name "PA28_USB_HOST_EN") (class "Default")
      (node (ref "IC1") (pin "41") (pinfunction "PA28/EIC_41") (pintype "bidirectional"))
      (node (ref "R10") (pin "2") (pinfunction "2_2") (pintype "passive"))
    )
    (net (code "49") (name "PA30_SWCLK") (class "Default")
      (node (ref "IC1") (pin "45") (pinfunction "PA30/EIC/SCOM1PAD2/TC1_45") (pintype "bidirectional"))
      (node (ref "SWD") (pin "4") (pinfunction "4_4") (pintype "passive"))
    )
    (net (code "50") (name "PA31_SWDIO") (class "Default")
      (node (ref "IC1") (pin "46") (pinfunction "PA31/EIC/SCOM1PAD3/TC1_46") (pintype "bidirectional"))
      (node (ref "SWD") (pin "2") (pinfunction "2_2") (pintype "passive"))
    )
    (net (code "51") (name "PB02_AIN10") (class "Default")
      (node (ref "IC1") (pin "47") (pinfunction "PB2/EIC/AIN10/SCOM5PAD0_47") (pintype "bidirectional"))
      (node (ref "R22") (pin "1") (pinfunction "1_1") (pintype "passive"))
      (node (ref "R23") (pin "2") (pinfunction "2_2") (pintype "passive"))
    )
    (net (code "52") (name "PB03_RX_LED") (class "Default")
      (node (ref "IC1") (pin "48") (pinfunction "PB3/EIC/AIN11/SCOM5PAD1_48") (pintype "bidirectional"))
    )
    (net (code "53") (name "PB08_AIN2") (class "Default")
      (node (ref "IC1") (pin "7") (pinfunction "PB8/EIC/AIN2/SCOM4PAD0/TC4_7") (pintype "bidirectional"))
      (node (ref "U$1") (pin "10") (pinfunction "Y_10") (pintype "power_in"))
    )
    (net (code "54") (name "PB09_AIN3") (class "Default")
      (node (ref "IC1") (pin "8") (pinfunction "PB9/EIC/AIN3/SCOM4PAD1//TC4_8") (pintype "bidirectional"))
      (node (ref "U$1") (pin "8") (pinfunction "Z_8") (pintype "power_in"))
    )
    (net (code "55") (name "PB10_S4_SPI_MOSI") (class "Default")
      (node (ref "IC1") (pin "19") (pinfunction "PB10/EIC/SCOM4PAD2/TC5_19") (pintype "bidirectional"))
    )
    (net (code "56") (name "PB11_S4_SPI_SCK") (class "Default")
      (node (ref "IC1") (pin "20") (pinfunction "PB11/EIC/SCOM4PAD3/TC5_20") (pintype "bidirectional"))
    )
    (net (code "57") (name "PB12_S4_SPI_MISO") (class "Default")
      (node (ref "IC1") (pin "21") (pinfunction "PA12/I2C/EIC/SCOM2PAD0+/TC2_21") (pintype "bidirectional"))
    )
    (net (code "58") (name "RESET") (class "Default")
      (node (ref "R1") (pin "1") (pinfunction "1_1") (pintype "passive"))
      (node (ref "R6") (pin "2") (pinfunction "2_2") (pintype "passive"))
      (node (ref "RESET") (pin "P$3") (pinfunction "P$3_P$3") (pintype "bidirectional"))
      (node (ref "SWD") (pin "10") (pinfunction "10_10") (pintype "passive"))
    )
    (net (code "59") (name "RXD") (class "Default")
      (node (ref "IC1") (pin "38") (pinfunction "PB23/EIC/SCOM5PAD3_38") (pintype "bidirectional"))
    )
    (net (code "60") (name "SCK{slash}D13") (class "Default")
      (node (ref "OLED") (pin "P$3") (pinfunction "SD_SCK_P$3") (pintype "bidirectional"))
      (node (ref "OLED") (pin "P$8") (pinfunction "OLED_SCK_P$8") (pintype "bidirectional"))
      (node (ref "R25") (pin "1") (pinfunction "1_1") (pintype "passive"))
    )
    (net (code "61") (name "SS{slash}D10") (class "Default")
      (node (ref "IC1") (pin "27") (pinfunction "PA18/EIC/SCOM1PAD2+/TC3_27") (pintype "bidirectional"))
      (node (ref "OLED") (pin "P$1") (pinfunction "SD_CS_P$1") (pintype "bidirectional"))
    )
    (net (code "62") (name "ST") (class "Default")
      (node (ref "U$1") (pin "2") (pinfunction "ST_2") (pintype "power_in"))
    )
    (net (code "63") (name "TARGET_RESET_EDBG") (class "Default")
      (node (ref "IC1") (pin "40") (pinfunction "RESETN_40") (pintype "bidirectional"))
      (node (ref "R6") (pin "1") (pinfunction "1_1") (pintype "passive"))
    )
    (net (code "64") (name "TARGET_USB_N") (class "Default")
      (node (ref "IC1") (pin "33") (pinfunction "PA24/EIC/SCOM3PAD2+/TC5_33") (pintype "bidirectional"))
      (node (ref "U$2") (pin "2") (pinfunction "D-_2") (pintype "bidirectional"))
    )
    (net (code "65") (name "TARGET_USB_P") (class "Default")
      (node (ref "IC1") (pin "34") (pinfunction "PA25/EIC/SCOM3PAD3+/TC5_34") (pintype "bidirectional"))
      (node (ref "U$2") (pin "3") (pinfunction "D+_3") (pintype "bidirectional"))
    )
    (net (code "66") (name "TXD") (class "Default")
      (node (ref "IC1") (pin "37") (pinfunction "PB22/EIC/SCOM5PAD2_37") (pintype "bidirectional"))
    )
    (net (code "67") (name "VBUS") (class "Default")
      (node (ref "C12") (pin "1") (pinfunction "1_1") (pintype "passive"))
      (node (ref "C6") (pin "1") (pinfunction "1_1") (pintype "passive"))
      (node (ref "IC3") (pin "8") (pinfunction "IN1_8") (pintype "bidirectional"))
      (node (ref "IC4") (pin "1") (pinfunction "OUT_1") (pintype "power_in"))
      (node (ref "MCP") (pin "P$4") (pinfunction "VDD_P$4") (pintype "bidirectional"))
      (node (ref "R12") (pin "1") (pinfunction "1_1") (pintype "passive"))
      (node (ref "R3") (pin "1") (pinfunction "1_1") (pintype "passive"))
      (node (ref "U$2") (pin "1") (pinfunction "VCC_1") (pintype "bidirectional"))
    )
    (net (code "68") (name "VCC_HC05") (class "Default")
      (node (ref "C21") (pin "1") (pinfunction "1_1") (pintype "passive"))
      (node (ref "HC06") (pin "P$4") (pinfunction "P$4_P$4") (pintype "bidirectional"))
      (node (ref "U$6") (pin "1") (pinfunction "VOUT_1") (pintype "bidirectional"))
    )
    (net (code "69") (name "VCC_OLED") (class "Default")
      (node (ref "C17") (pin "1") (pinfunction "1_1") (pintype "passive"))
      (node (ref "OLED") (pin "P$11") (pinfunction "VCC_P$11") (pintype "bidirectional"))
      (node (ref "U$3") (pin "1") (pinfunction "VOUT_1") (pintype "bidirectional"))
    )
    (net (code "70") (name "VIN") (class "Default")
      (node (ref "BATT") (pin "2") (pinfunction "2_2") (pintype "passive"))
      (node (ref "C13") (pin "1") (pinfunction "1_1") (pintype "passive"))
      (node (ref "C18") (pin "1") (pinfunction "1_1") (pintype "passive"))
      (node (ref "IC3") (pin "6") (pinfunction "IN2_6") (pintype "bidirectional"))
      (node (ref "IC4") (pin "3") (pinfunction "IN_3") (pintype "power_in"))
      (node (ref "MCP") (pin "P$3") (pinfunction "VBAT_P$3") (pintype "bidirectional"))
      (node (ref "R20") (pin "2") (pinfunction "2_2") (pintype "passive"))
      (node (ref "U$3") (pin "5") (pinfunction "VIN_5") (pintype "bidirectional"))
      (node (ref "U$6") (pin "5") (pinfunction "VIN_5") (pintype "bidirectional"))
    )
    (net (code "71") (name "VMAIN") (class "Default")
      (node (ref "IC3") (pin "7") (pinfunction "OUT_7") (pintype "bidirectional"))
      (node (ref "TPS") (pin "5") (pinfunction "VIN_5") (pintype "input"))
      (node (ref "TPS") (pin "6") (pinfunction "EN_6") (pintype "input"))
      (node (ref "TPS") (pin "7") (pinfunction "PS/SYNC_7") (pintype "input"))
      (node (ref "TPS") (pin "8") (pinfunction "VINA_8") (pintype "input"))
    )
    (net (code "72") (name "unconnected-(D2-Pad1)") (class "Default")
      (node (ref "D2") (pin "1") (pinfunction "1_1") (pintype "bidirectional"))
    )
    (net (code "73") (name "unconnected-(D3-Pad1)") (class "Default")
      (node (ref "D3") (pin "1") (pinfunction "1_1") (pintype "bidirectional"))
    )
    (net (code "74") (name "unconnected-(D4-Pad1)") (class "Default")
      (node (ref "D4") (pin "1") (pinfunction "1_1") (pintype "bidirectional"))
    )
    (net (code "75") (name "unconnected-(D5-Pad1)") (class "Default")
      (node (ref "D5") (pin "1") (pinfunction "1_1") (pintype "bidirectional"))
    )
    (net (code "76") (name "unconnected-(IC1-PA22{slash}I2C{slash}EIC{slash}SCOM5PAD0+{slash}TC4-Pad31)") (class "Default")
      (node (ref "IC1") (pin "31") (pinfunction "PA22/I2C/EIC/SCOM5PAD0+/TC4_31") (pintype "bidirectional"))
    )
    (net (code "77") (name "unconnected-(IC1-PA23{slash}I2C{slash}EIC{slash}SCOM5PAD1+{slash}TC4-Pad32)") (class "Default")
      (node (ref "IC1") (pin "32") (pinfunction "PA23/I2C/EIC/SCOM5PAD1+/TC4_32") (pintype "bidirectional"))
    )
    (net (code "78") (name "unconnected-(IC3-STAT-Pad1)") (class "Default")
      (node (ref "IC3") (pin "1") (pinfunction "STAT_1") (pintype "bidirectional"))
    )
    (net (code "79") (name "unconnected-(RESET-PadP$2)") (class "Default")
      (node (ref "RESET") (pin "P$2") (pinfunction "P$2_P$2") (pintype "bidirectional"))
    )
    (net (code "80") (name "unconnected-(RESET-PadP$4)") (class "Default")
      (node (ref "RESET") (pin "P$4") (pinfunction "P$4_P$4") (pintype "bidirectional"))
    )
    (net (code "81") (name "unconnected-(SWD-Pad6)") (class "Default")
      (node (ref "SWD") (pin "6") (pinfunction "6_6") (pintype "passive"))
    )
    (net (code "82") (name "unconnected-(SWD-Pad7)") (class "Default")
      (node (ref "SWD") (pin "7") (pinfunction "7_7") (pintype "passive"))
    )
    (net (code "83") (name "unconnected-(SWD-Pad8)") (class "Default")
      (node (ref "SWD") (pin "8") (pinfunction "8_8") (pintype "passive"))
    )
  )
)
